# PA.net
KiCad netlist of a schematic drawn in EAGLE
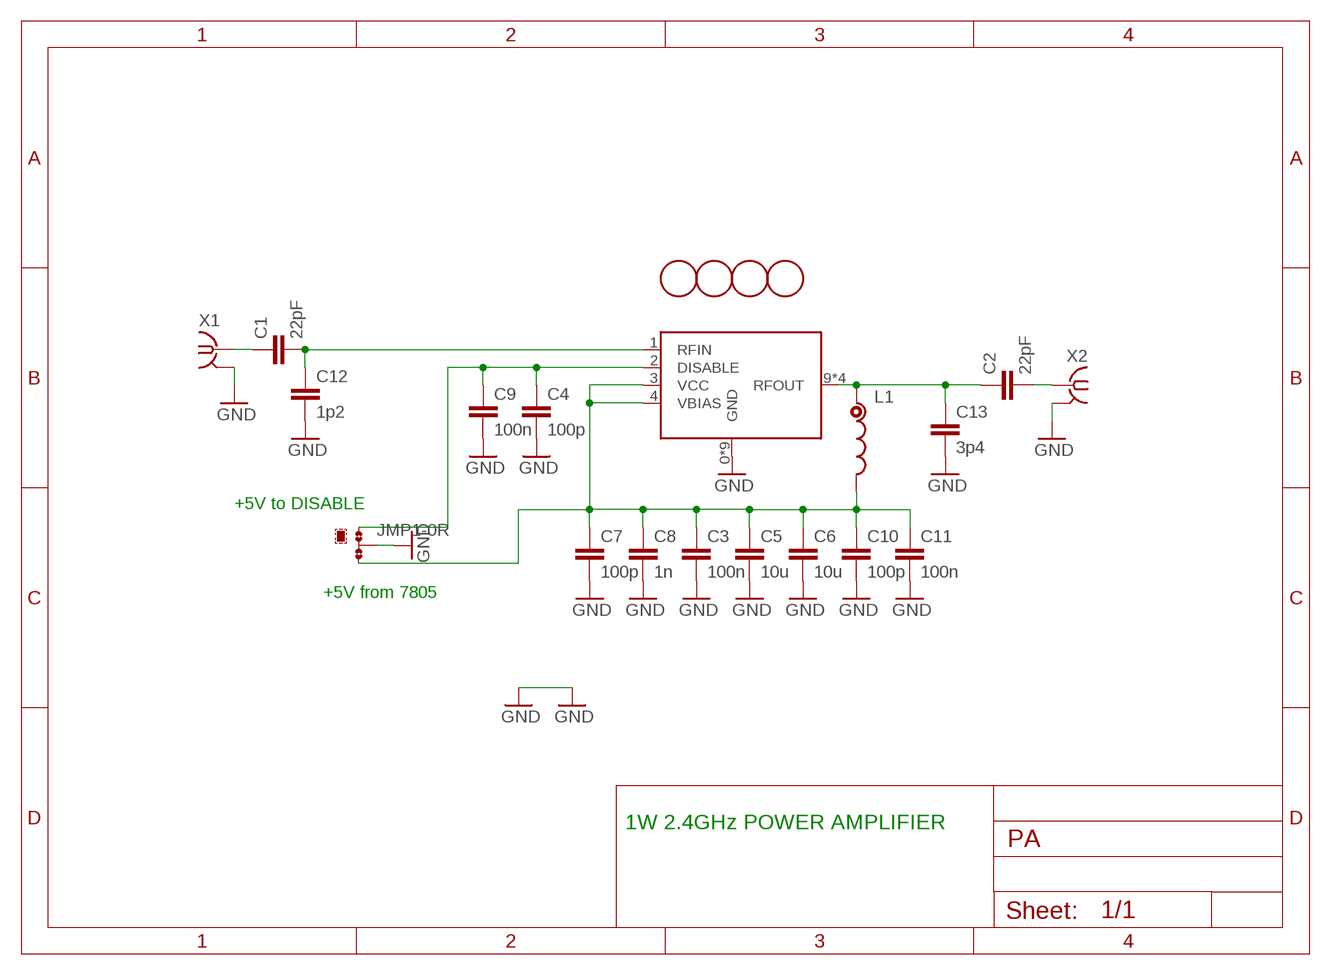
[diagram p0: schematic, sheet 1]

(export (version "E")
  (design (tool "Eeschema 10.0.6"))
  (components
    (comp (ref "C1")
      (value "22pF")
      (footprint "eagle-import:C0603")
      (libsource (lib "eagle-import") (part "C-EUC0603"))
    )
    (comp (ref "C2")
      (value "22pF")
      (footprint "eagle-import:C0603")
      (libsource (lib "eagle-import") (part "C-EUC0603"))
    )
    (comp (ref "C3")
      (value "100n")
      (footprint "eagle-import:C0603")
      (libsource (lib "eagle-import") (part "C-EUC0603"))
    )
    (comp (ref "C4")
      (value "100p")
      (footprint "eagle-import:C0603")
      (libsource (lib "eagle-import") (part "C-EUC0603"))
    )
    (comp (ref "C5")
      (value "10u")
      (footprint "eagle-import:C1210")
      (libsource (lib "eagle-import") (part "C-EUC1210"))
    )
    (comp (ref "C6")
      (value "10u")
      (footprint "eagle-import:C1210")
      (libsource (lib "eagle-import") (part "C-EUC1210"))
    )
    (comp (ref "C7")
      (value "100p")
      (footprint "eagle-import:C0603")
      (libsource (lib "eagle-import") (part "C-EUC0603"))
    )
    (comp (ref "C8")
      (value "1n")
      (footprint "eagle-import:C0603")
      (libsource (lib "eagle-import") (part "C-EUC0603"))
    )
    (comp (ref "C9")
      (value "100n")
      (footprint "eagle-import:C0603")
      (libsource (lib "eagle-import") (part "C-EUC0603"))
    )
    (comp (ref "C10")
      (value "100p")
      (footprint "eagle-import:C0603")
      (libsource (lib "eagle-import") (part "C-EUC0603"))
    )
    (comp (ref "C11")
      (value "100n")
      (footprint "eagle-import:C0603")
      (libsource (lib "eagle-import") (part "C-EUC0603"))
    )
    (comp (ref "C12")
      (value "1p2")
      (footprint "eagle-import:C0603")
      (libsource (lib "eagle-import") (part "C-EUC0603"))
    )
    (comp (ref "C13")
      (value "3p4")
      (footprint "eagle-import:C0603")
      (libsource (lib "eagle-import") (part "C-EUC0603"))
    )
    (comp (ref "JMP1")
      (value "0R-JUMPB")
      (footprint "eagle-import:B0R-JMP")
      (libsource (lib "eagle-import") (part "0R-JUMPB"))
    )
    (comp (ref "L1")
      (value "INDUCTOR0603")
      (footprint "eagle-import:0603")
      (libsource (lib "eagle-import") (part "INDUCTOR0603"))
    )
    (comp (ref "U$1")
      (value "ADL5606")
      (footprint "eagle-import:LFCSP-16-4X4")
      (libsource (lib "eagle-import") (part "ADL5606"))
    )
    (comp (ref "U$2")
      (value "FIDUCIAL")
      (footprint "eagle-import:FIDUCIAL_1MM")
      (libsource (lib "eagle-import") (part "FIDUCIAL"))
    )
    (comp (ref "U$3")
      (value "FIDUCIAL")
      (footprint "eagle-import:FIDUCIAL_1MM")
      (libsource (lib "eagle-import") (part "FIDUCIAL"))
    )
    (comp (ref "U$4")
      (value "FIDUCIAL")
      (footprint "eagle-import:FIDUCIAL_1MM")
      (libsource (lib "eagle-import") (part "FIDUCIAL"))
    )
    (comp (ref "U$5")
      (value "FIDUCIAL")
      (footprint "eagle-import:FIDUCIAL_1MM")
      (libsource (lib "eagle-import") (part "FIDUCIAL"))
    )
    (comp (ref "X1")
      (value "SMA-142-0711-821/826")
      (footprint "eagle-import:J502-ND-142-0711-821_826")
      (fields (field (name "MF") "JOHNSON COMPONENTS") (field (name "MPN") "142-0711-821"))
      (libsource (lib "eagle-import") (part "SMA-142-0711-821/826"))
    )
    (comp (ref "X2")
      (value "SMA-142-0711-821/826")
      (footprint "eagle-import:J502-ND-142-0711-821_826")
      (fields (field (name "MF") "JOHNSON COMPONENTS") (field (name "MPN") "142-0711-821"))
      (libsource (lib "eagle-import") (part "SMA-142-0711-821/826"))
    )
  )
  (nets
    (net (code "1") (name "GND") (class "Default")
      (node (ref "C10") (pin "2") (pinfunction "2_2") (pintype "passive"))
      (node (ref "C11") (pin "2") (pinfunction "2_2") (pintype "passive"))
      (node (ref "C12") (pin "2") (pinfunction "2_2") (pintype "passive"))
      (node (ref "C13") (pin "2") (pinfunction "2_2") (pintype "passive"))
      (node (ref "C3") (pin "2") (pinfunction "2_2") (pintype "passive"))
      (node (ref "C4") (pin "2") (pinfunction "2_2") (pintype "passive"))
      (node (ref "C5") (pin "2") (pinfunction "2_2") (pintype "passive"))
      (node (ref "C6") (pin "2") (pinfunction "2_2") (pintype "passive"))
      (node (ref "C7") (pin "2") (pinfunction "2_2") (pintype "passive"))
      (node (ref "C8") (pin "2") (pinfunction "2_2") (pintype "passive"))
      (node (ref "C9") (pin "2") (pinfunction "2_2") (pintype "passive"))
      (node (ref "JMP1") (pin "2") (pinfunction "2_2") (pintype "passive"))
      (node (ref "U$1") (pin "0") (pinfunction "GND_0") (pintype "bidirectional"))
      (node (ref "U$1") (pin "13") (pinfunction "GND_13") (pintype "bidirectional"))
      (node (ref "U$1") (pin "14") (pinfunction "GND_14") (pintype "bidirectional"))
      (node (ref "U$1") (pin "15") (pinfunction "GND_15") (pintype "bidirectional"))
      (node (ref "U$1") (pin "16") (pinfunction "GND_16") (pintype "bidirectional"))
      (node (ref "U$1") (pin "5") (pinfunction "GND_5") (pintype "bidirectional"))
      (node (ref "U$1") (pin "6") (pinfunction "GND_6") (pintype "bidirectional"))
      (node (ref "U$1") (pin "7") (pinfunction "GND_7") (pintype "bidirectional"))
      (node (ref "U$1") (pin "8") (pinfunction "GND_8") (pintype "bidirectional"))
      (node (ref "X1") (pin "G@1") (pinfunction "2_G@1") (pintype "passive"))
      (node (ref "X1") (pin "G@2") (pinfunction "2_G@2") (pintype "passive"))
      (node (ref "X1") (pin "G@3") (pinfunction "2_G@3") (pintype "passive"))
      (node (ref "X1") (pin "G@4") (pinfunction "2_G@4") (pintype "passive"))
      (node (ref "X2") (pin "G@1") (pinfunction "2_G@1") (pintype "passive"))
      (node (ref "X2") (pin "G@2") (pinfunction "2_G@2") (pintype "passive"))
      (node (ref "X2") (pin "G@3") (pinfunction "2_G@3") (pintype "passive"))
      (node (ref "X2") (pin "G@4") (pinfunction "2_G@4") (pintype "passive"))
    )
    (net (code "2") (name "Net-(C1-Pad1)") (class "Default")
      (node (ref "C1") (pin "1") (pinfunction "1_1") (pintype "passive"))
      (node (ref "X1") (pin "1") (pinfunction "1_1") (pintype "passive"))
    )
    (net (code "3") (name "Net-(C2-Pad2)") (class "Default")
      (node (ref "C2") (pin "2") (pinfunction "2_2") (pintype "passive"))
      (node (ref "X2") (pin "1") (pinfunction "1_1") (pintype "passive"))
    )
    (net (code "4") (name "Net-(C13-Pad1)") (class "Default")
      (node (ref "C13") (pin "1") (pinfunction "1_1") (pintype "passive"))
      (node (ref "C2") (pin "1") (pinfunction "1_1") (pintype "passive"))
      (node (ref "L1") (pin "1") (pinfunction "1_1") (pintype "passive"))
      (node (ref "U$1") (pin "10") (pinfunction "RFOUT_10") (pintype "bidirectional"))
      (node (ref "U$1") (pin "11") (pinfunction "RFOUT_11") (pintype "bidirectional"))
      (node (ref "U$1") (pin "12") (pinfunction "RFOUT_12") (pintype "bidirectional"))
      (node (ref "U$1") (pin "9") (pinfunction "RFOUT_9") (pintype "bidirectional"))
    )
    (net (code "5") (name "Net-(U$1-DISABLE)") (class "Default")
      (node (ref "C4") (pin "1") (pinfunction "1_1") (pintype "passive"))
      (node (ref "C9") (pin "1") (pinfunction "1_1") (pintype "passive"))
      (node (ref "JMP1") (pin "1") (pinfunction "1_1") (pintype "passive"))
      (node (ref "U$1") (pin "2") (pinfunction "DISABLE_2") (pintype "bidirectional"))
    )
    (net (code "6") (name "Net-(U$1-RFIN)") (class "Default")
      (node (ref "C1") (pin "2") (pinfunction "2_2") (pintype "passive"))
      (node (ref "C12") (pin "1") (pinfunction "1_1") (pintype "passive"))
      (node (ref "U$1") (pin "1") (pinfunction "RFIN_1") (pintype "bidirectional"))
    )
    (net (code "7") (name "Net-(U$1-VBIAS)") (class "Default")
      (node (ref "C10") (pin "1") (pinfunction "1_1") (pintype "passive"))
      (node (ref "C11") (pin "1") (pinfunction "1_1") (pintype "passive"))
      (node (ref "C3") (pin "1") (pinfunction "1_1") (pintype "passive"))
      (node (ref "C5") (pin "1") (pinfunction "1_1") (pintype "passive"))
      (node (ref "C6") (pin "1") (pinfunction "1_1") (pintype "passive"))
      (node (ref "C7") (pin "1") (pinfunction "1_1") (pintype "passive"))
      (node (ref "C8") (pin "1") (pinfunction "1_1") (pintype "passive"))
      (node (ref "JMP1") (pin "3") (pinfunction "3_3") (pintype "passive"))
      (node (ref "L1") (pin "2") (pinfunction "2_2") (pintype "passive"))
      (node (ref "U$1") (pin "3") (pinfunction "VCC_3") (pintype "bidirectional"))
      (node (ref "U$1") (pin "4") (pinfunction "VBIAS_4") (pintype "bidirectional"))
    )
  )
)
